# STM32F407_2.net
KiCad netlist of a schematic drawn in Altium Designer
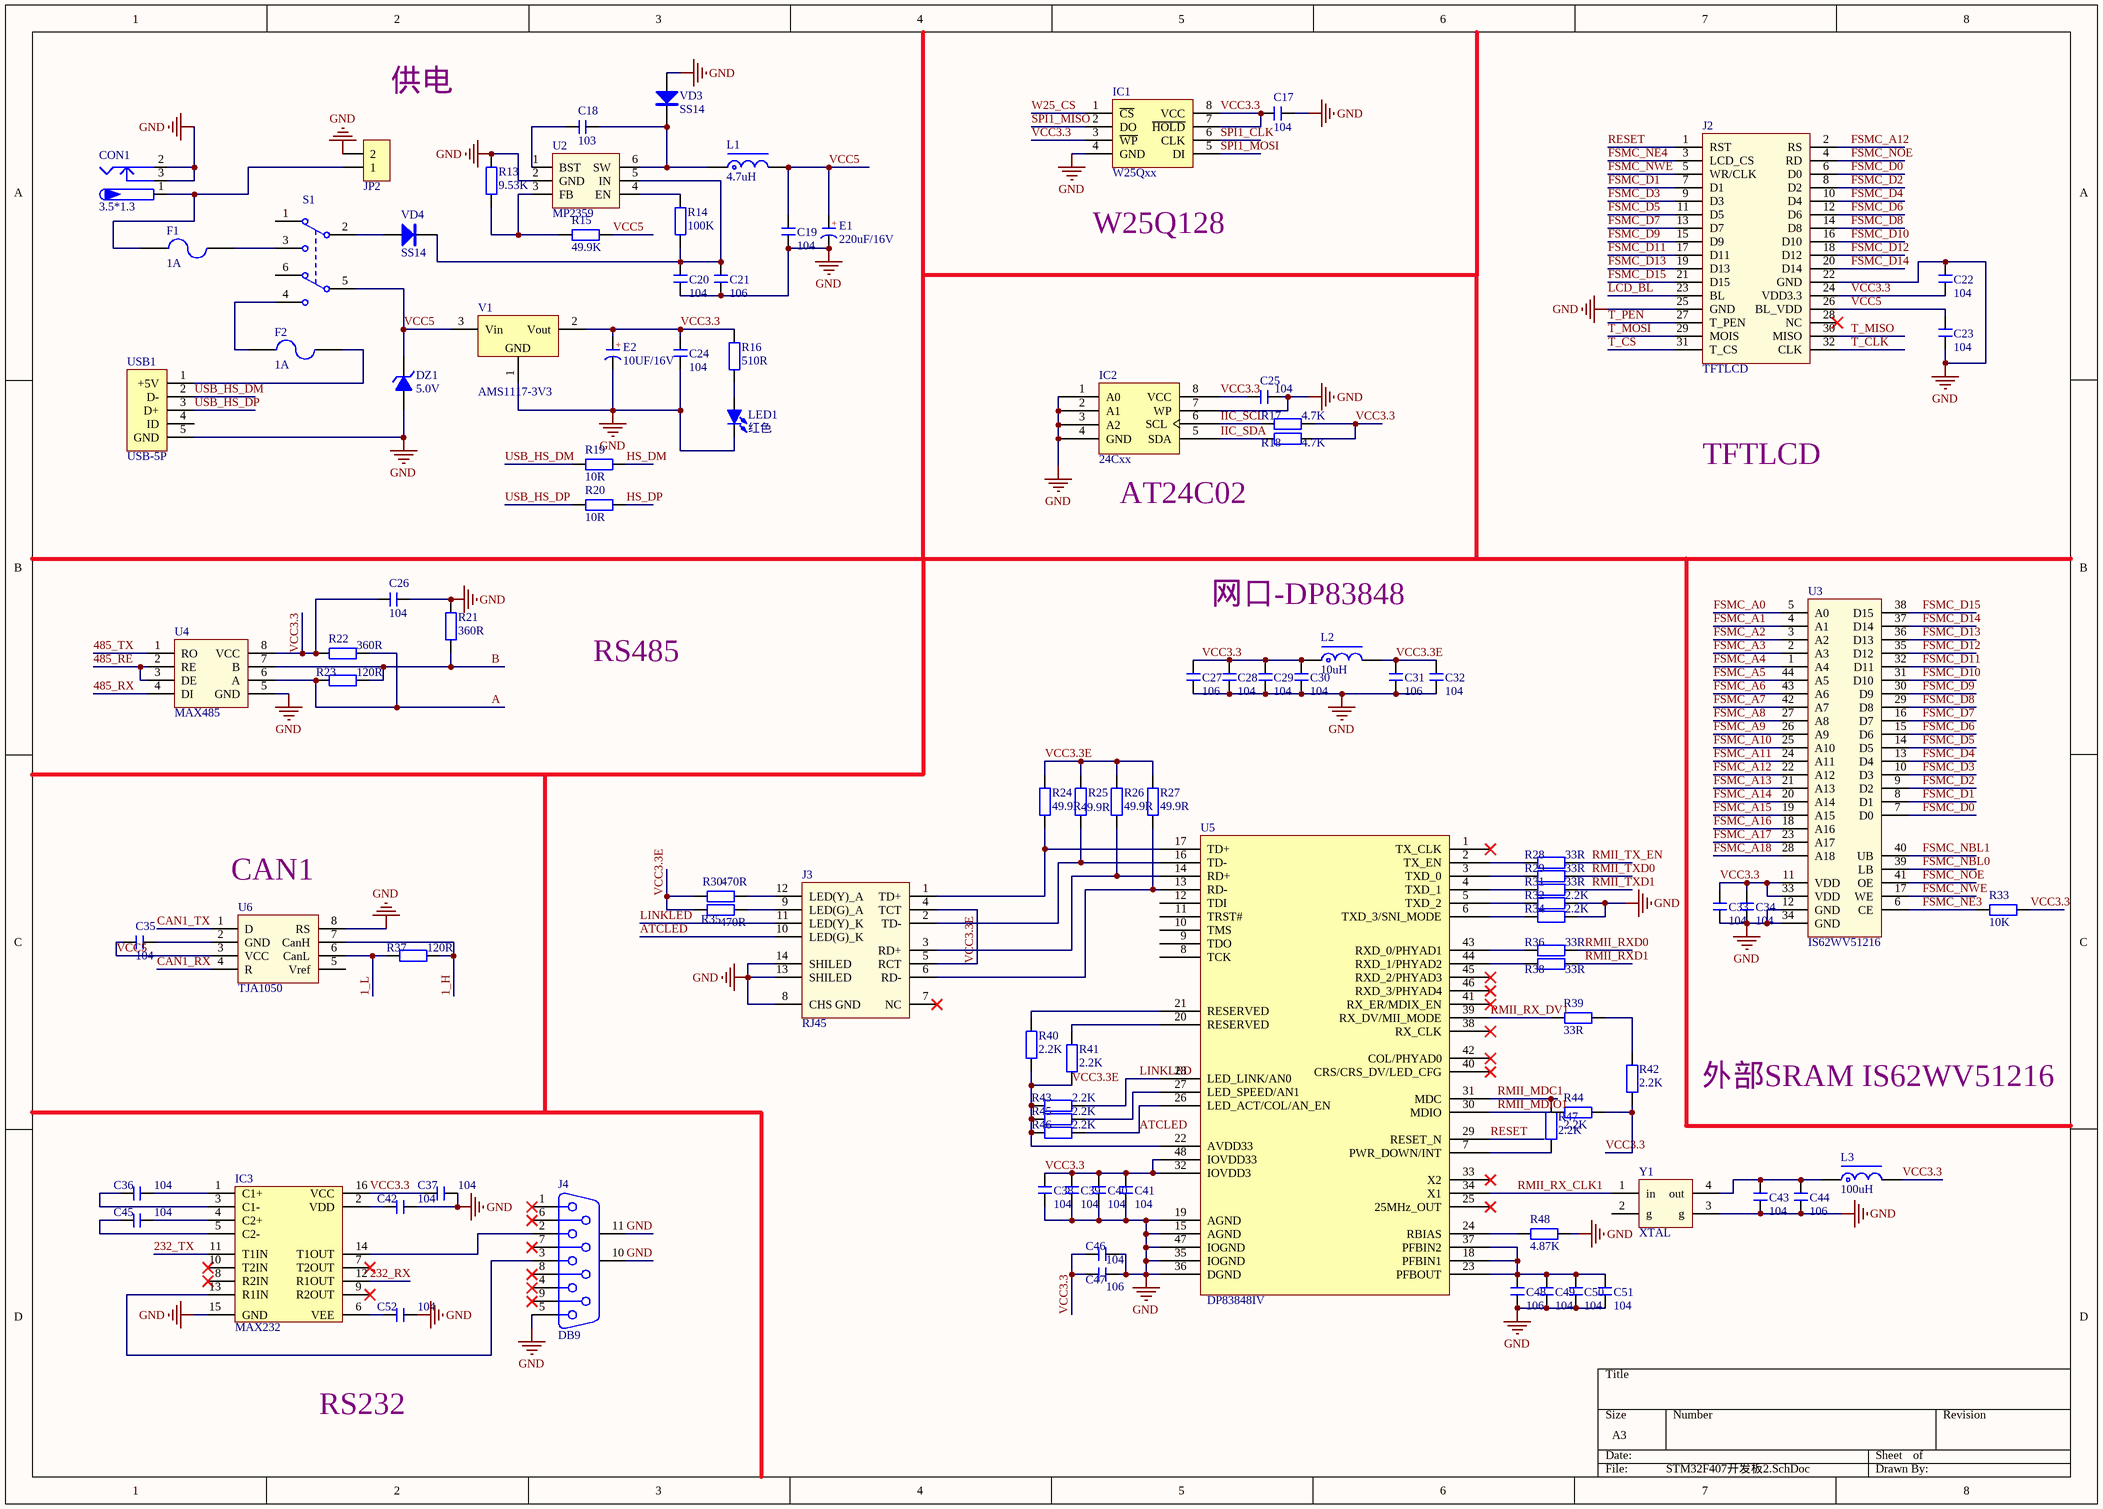
[diagram p0: STM32F407开发板2.SchDoc]

(export (version "E")
  (design (tool "Eeschema 10.0.6"))
  (components
    (comp (ref "C17")
      (value "104")
      (footprint "C 0603")
      (description "无极性贴片电容")
      (libsource (lib "电阻-电容-电感") (part "C"))
    )
    (comp (ref "C18")
      (value "103")
      (footprint "C 0603")
      (description "无极性贴片电容")
      (libsource (lib "电阻-电容-电感") (part "C"))
    )
    (comp (ref "C19")
      (value "104")
      (footprint "C 0603")
      (description "无极性贴片电容")
      (libsource (lib "电阻-电容-电感") (part "C"))
    )
    (comp (ref "C20")
      (value "104")
      (footprint "C 0603")
      (description "无极性贴片电容")
      (libsource (lib "电阻-电容-电感") (part "C"))
    )
    (comp (ref "C21")
      (value "106")
      (footprint "C 0603")
      (description "无极性贴片电容")
      (libsource (lib "电阻-电容-电感") (part "C"))
    )
    (comp (ref "C22")
      (value "104")
      (footprint "C 0603")
      (description "无极性贴片电容")
      (libsource (lib "电阻-电容-电感") (part "C"))
    )
    (comp (ref "C23")
      (value "104")
      (footprint "C 0603")
      (description "无极性贴片电容")
      (libsource (lib "电阻-电容-电感") (part "C"))
    )
    (comp (ref "C24")
      (value "104")
      (footprint "C 0603")
      (description "无极性贴片电容")
      (libsource (lib "电阻-电容-电感") (part "C"))
    )
    (comp (ref "C25")
      (value "104")
      (footprint "C 0603")
      (description "无极性贴片电容")
      (libsource (lib "电阻-电容-电感") (part "C"))
    )
    (comp (ref "C26")
      (value "104")
      (footprint "C 0603")
      (description "无极性贴片电容")
      (libsource (lib "电阻-电容-电感") (part "C"))
    )
    (comp (ref "C27")
      (value "106")
      (footprint "C 0603")
      (description "无极性贴片电容")
      (libsource (lib "电阻-电容-电感") (part "C"))
    )
    (comp (ref "C28")
      (value "104")
      (footprint "C 0603")
      (description "无极性贴片电容")
      (libsource (lib "电阻-电容-电感") (part "C"))
    )
    (comp (ref "C29")
      (value "104")
      (footprint "C 0603")
      (description "无极性贴片电容")
      (libsource (lib "电阻-电容-电感") (part "C"))
    )
    (comp (ref "C30")
      (value "104")
      (footprint "C 0603")
      (description "无极性贴片电容")
      (libsource (lib "电阻-电容-电感") (part "C"))
    )
    (comp (ref "C31")
      (value "106")
      (footprint "C 0603")
      (description "无极性贴片电容")
      (libsource (lib "电阻-电容-电感") (part "C"))
    )
    (comp (ref "C32")
      (value "104")
      (footprint "C 0603")
      (description "无极性贴片电容")
      (libsource (lib "电阻-电容-电感") (part "C"))
    )
    (comp (ref "C33")
      (value "104")
      (footprint "C 0603")
      (description "无极性贴片电容")
      (libsource (lib "电阻-电容-电感") (part "C"))
    )
    (comp (ref "C34")
      (value "104")
      (footprint "C 0603")
      (description "无极性贴片电容")
      (libsource (lib "电阻-电容-电感") (part "C"))
    )
    (comp (ref "C35")
      (value "104")
      (footprint "C 0603")
      (description "无极性贴片电容")
      (libsource (lib "电阻-电容-电感") (part "C"))
    )
    (comp (ref "C36")
      (value "104")
      (footprint "C 0603")
      (description "无极性贴片电容")
      (libsource (lib "电阻-电容-电感") (part "C"))
    )
    (comp (ref "C37")
      (value "104")
      (footprint "C 0603")
      (description "无极性贴片电容")
      (libsource (lib "电阻-电容-电感") (part "C"))
    )
    (comp (ref "C38")
      (value "104")
      (footprint "C 0603")
      (description "无极性贴片电容")
      (libsource (lib "电阻-电容-电感") (part "C"))
    )
    (comp (ref "C39")
      (value "104")
      (footprint "C 0603")
      (description "无极性贴片电容")
      (libsource (lib "电阻-电容-电感") (part "C"))
    )
    (comp (ref "C40")
      (value "104")
      (footprint "C 0603")
      (description "无极性贴片电容")
      (libsource (lib "电阻-电容-电感") (part "C"))
    )
    (comp (ref "C41")
      (value "104")
      (footprint "C 0603")
      (description "无极性贴片电容")
      (libsource (lib "电阻-电容-电感") (part "C"))
    )
    (comp (ref "C42")
      (value "104")
      (footprint "C 0603")
      (description "无极性贴片电容")
      (libsource (lib "电阻-电容-电感") (part "C"))
    )
    (comp (ref "C43")
      (value "104")
      (footprint "C 0603")
      (description "无极性贴片电容")
      (libsource (lib "电阻-电容-电感") (part "C"))
    )
    (comp (ref "C44")
      (value "106")
      (footprint "C 0603")
      (description "无极性贴片电容")
      (libsource (lib "电阻-电容-电感") (part "C"))
    )
    (comp (ref "C45")
      (value "104")
      (footprint "C 0603")
      (description "无极性贴片电容")
      (libsource (lib "电阻-电容-电感") (part "C"))
    )
    (comp (ref "C46")
      (value "104")
      (footprint "C 0603")
      (description "无极性贴片电容")
      (libsource (lib "电阻-电容-电感") (part "C"))
    )
    (comp (ref "C47")
      (value "106")
      (footprint "C 0603")
      (description "无极性贴片电容")
      (libsource (lib "电阻-电容-电感") (part "C"))
    )
    (comp (ref "C48")
      (value "106")
      (footprint "C 0603")
      (description "无极性贴片电容")
      (libsource (lib "电阻-电容-电感") (part "C"))
    )
    (comp (ref "C49")
      (value "104")
      (footprint "C 0603")
      (description "无极性贴片电容")
      (libsource (lib "电阻-电容-电感") (part "C"))
    )
    (comp (ref "C50")
      (value "104")
      (footprint "C 0603")
      (description "无极性贴片电容")
      (libsource (lib "电阻-电容-电感") (part "C"))
    )
    (comp (ref "C51")
      (value "104")
      (footprint "C 0603")
      (description "无极性贴片电容")
      (libsource (lib "电阻-电容-电感") (part "C"))
    )
    (comp (ref "C52")
      (value "104")
      (footprint "C 0603")
      (description "无极性贴片电容")
      (libsource (lib "电阻-电容-电感") (part "C"))
    )
    (comp (ref "CON1")
      (value "3.5*1.3")
      (footprint "DC_5.5MM")
      (description "低压电源接口")
      (libsource (lib "接口类") (part "P-DC"))
    )
    (comp (ref "DZ1")
      (value "5.0V")
      (footprint "MINI_MELF (LL34)")
      (description "12V/0.5W稳压管")
      (libsource (lib "二极管-整流桥") (part "1N4106"))
    )
    (comp (ref "E1")
      (value "220uF/16V")
      (footprint "CM D(6.3*7.7)")
      (description "直插电解电容")
      (libsource (lib "电阻-电容-电感") (part "C-CAP"))
    )
    (comp (ref "E2")
      (value "10UF/16V")
      (footprint "C 1206")
      (description "直插电解电容")
      (libsource (lib "电阻-电容-电感") (part "C-CAP"))
    )
    (comp (ref "F1")
      (value "1A")
      (footprint "L 1206")
      (description "5*20保险丝")
      (libsource (lib "保险丝-晶振") (part "FU 5x20"))
    )
    (comp (ref "F2")
      (value "1A")
      (footprint "L 1206")
      (description "5*20保险丝")
      (libsource (lib "保险丝-晶振") (part "FU 5x20"))
    )
    (comp (ref "IC1")
      (value "W25Qxx")
      (footprint "SOP8W_L")
      (description "外置Flash")
      (libsource (lib "IC芯片") (part "W25Qxx"))
    )
    (comp (ref "IC2")
      (value "24Cxx")
      (footprint "SOP8_L")
      (description "外置EEPROM")
      (libsource (lib "IC芯片") (part "24Cxx"))
    )
    (comp (ref "IC3") (value "MAX232") (footprint "SOP16_L") (libsource (lib "IC芯片") (part "MAX232")))
    (comp (ref "J2") (value "TFTLCD") (footprint "HDR-16X2") (libsource (lib "显示器件") (part "TFTLCD")))
    (comp (ref "J3") (value "RJ45") (footprint "HR911105A") (libsource (lib "IC芯片") (part "RJ45")))
    (comp (ref "J4")
      (value "DB9")
      (footprint "DB9/P_A")
      (description "9针串口")
      (libsource (lib "接口类") (part "DB9"))
    )
    (comp (ref "JP2")
      (value "HDR-1X2")
      (footprint "KF301-2P")
      (description "2P接插件")
      (libsource (lib "接插件") (part "Header 2"))
    )
    (comp (ref "L1")
      (value "4.7uH")
      (footprint "L 0603")
      (description "小功率贴片电感")
      (libsource (lib "电阻-电容-电感") (part "L"))
    )
    (comp (ref "L2")
      (value "10uH")
      (footprint "L 0603")
      (description "小功率贴片电感")
      (libsource (lib "电阻-电容-电感") (part "L"))
    )
    (comp (ref "L3")
      (value "100uH")
      (footprint "L 0603")
      (description "小功率贴片电感")
      (libsource (lib "电阻-电容-电感") (part "L"))
    )
    (comp (ref "LED1")
      (value "红色")
      (footprint "LED 0603R")
      (description "5mm插件LED")
      (libsource (lib "LED") (part "LED-5MM"))
    )
    (comp (ref "R13")
      (value "9.53K")
      (footprint "R 0603")
      (description "贴片电阻")
      (libsource (lib "电阻-电容-电感") (part "R"))
    )
    (comp (ref "R14")
      (value "100K")
      (footprint "R 0603")
      (description "贴片电阻")
      (libsource (lib "电阻-电容-电感") (part "R"))
    )
    (comp (ref "R15")
      (value "49.9K")
      (footprint "R 0603")
      (description "贴片电阻")
      (libsource (lib "电阻-电容-电感") (part "R"))
    )
    (comp (ref "R16")
      (value "510R")
      (footprint "R 0603")
      (description "贴片电阻")
      (libsource (lib "电阻-电容-电感") (part "R"))
    )
    (comp (ref "R17")
      (value "4.7K")
      (footprint "R 0603")
      (description "贴片电阻")
      (libsource (lib "电阻-电容-电感") (part "R"))
    )
    (comp (ref "R18")
      (value "4.7K")
      (footprint "R 0603")
      (description "贴片电阻")
      (libsource (lib "电阻-电容-电感") (part "R"))
    )
    (comp (ref "R19")
      (value "10R")
      (footprint "R 0603")
      (description "贴片电阻")
      (libsource (lib "电阻-电容-电感") (part "R"))
    )
    (comp (ref "R20")
      (value "10R")
      (footprint "R 0603")
      (description "贴片电阻")
      (libsource (lib "电阻-电容-电感") (part "R"))
    )
    (comp (ref "R21")
      (value "360R")
      (footprint "R 0603")
      (description "贴片电阻")
      (libsource (lib "电阻-电容-电感") (part "R"))
    )
    (comp (ref "R22")
      (value "360R")
      (footprint "R 0603")
      (description "贴片电阻")
      (libsource (lib "电阻-电容-电感") (part "R"))
    )
    (comp (ref "R23")
      (value "120R")
      (footprint "R 0603")
      (description "贴片电阻")
      (libsource (lib "电阻-电容-电感") (part "R"))
    )
    (comp (ref "R24")
      (value "49.9R")
      (footprint "R 0603")
      (description "贴片电阻")
      (libsource (lib "电阻-电容-电感") (part "R"))
    )
    (comp (ref "R25")
      (value "49.9R")
      (footprint "R 0603")
      (description "贴片电阻")
      (libsource (lib "电阻-电容-电感") (part "R"))
    )
    (comp (ref "R26")
      (value "49.9R")
      (footprint "R 0603")
      (description "贴片电阻")
      (libsource (lib "电阻-电容-电感") (part "R"))
    )
    (comp (ref "R27")
      (value "49.9R")
      (footprint "R 0603")
      (description "贴片电阻")
      (libsource (lib "电阻-电容-电感") (part "R"))
    )
    (comp (ref "R28")
      (value "33R")
      (footprint "R 0603")
      (description "贴片电阻")
      (libsource (lib "电阻-电容-电感") (part "R"))
    )
    (comp (ref "R29")
      (value "33R")
      (footprint "R 0603")
      (description "贴片电阻")
      (libsource (lib "电阻-电容-电感") (part "R"))
    )
    (comp (ref "R30")
      (value "470R")
      (footprint "R 0603")
      (description "贴片电阻")
      (libsource (lib "电阻-电容-电感") (part "R"))
    )
    (comp (ref "R31")
      (value "33R")
      (footprint "R 0603")
      (description "贴片电阻")
      (libsource (lib "电阻-电容-电感") (part "R"))
    )
    (comp (ref "R32")
      (value "2.2K")
      (footprint "R 0603")
      (description "贴片电阻")
      (libsource (lib "电阻-电容-电感") (part "R"))
    )
    (comp (ref "R33")
      (value "10K")
      (footprint "R 0603")
      (description "贴片电阻")
      (libsource (lib "电阻-电容-电感") (part "R"))
    )
    (comp (ref "R34")
      (value "2.2K")
      (footprint "R 0603")
      (description "贴片电阻")
      (libsource (lib "电阻-电容-电感") (part "R"))
    )
    (comp (ref "R35")
      (value "470R")
      (footprint "R 0603")
      (description "贴片电阻")
      (libsource (lib "电阻-电容-电感") (part "R"))
    )
    (comp (ref "R36")
      (value "33R")
      (footprint "R 0603")
      (description "贴片电阻")
      (libsource (lib "电阻-电容-电感") (part "R"))
    )
    (comp (ref "R37")
      (value "120R")
      (footprint "R 0603")
      (description "贴片电阻")
      (libsource (lib "电阻-电容-电感") (part "R"))
    )
    (comp (ref "R38")
      (value "33R")
      (footprint "R 0603")
      (description "贴片电阻")
      (libsource (lib "电阻-电容-电感") (part "R"))
    )
    (comp (ref "R39")
      (value "33R")
      (footprint "R 0603")
      (description "贴片电阻")
      (libsource (lib "电阻-电容-电感") (part "R"))
    )
    (comp (ref "R40")
      (value "2.2K")
      (footprint "R 0603")
      (description "贴片电阻")
      (libsource (lib "电阻-电容-电感") (part "R"))
    )
    (comp (ref "R41")
      (value "2.2K")
      (footprint "R 0603")
      (description "贴片电阻")
      (libsource (lib "电阻-电容-电感") (part "R"))
    )
    (comp (ref "R42")
      (value "2.2K")
      (footprint "R 0603")
      (description "贴片电阻")
      (libsource (lib "电阻-电容-电感") (part "R"))
    )
    (comp (ref "R43")
      (value "2.2K")
      (footprint "R 0603")
      (description "贴片电阻")
      (libsource (lib "电阻-电容-电感") (part "R"))
    )
    (comp (ref "R44")
      (value "2.2K")
      (footprint "R 0603")
      (description "贴片电阻")
      (libsource (lib "电阻-电容-电感") (part "R"))
    )
    (comp (ref "R45")
      (value "2.2K")
      (footprint "R 0603")
      (description "贴片电阻")
      (libsource (lib "电阻-电容-电感") (part "R"))
    )
    (comp (ref "R46")
      (value "2.2K")
      (footprint "R 0603")
      (description "贴片电阻")
      (libsource (lib "电阻-电容-电感") (part "R"))
    )
    (comp (ref "R47")
      (value "2.2K")
      (footprint "R 0603")
      (description "贴片电阻")
      (libsource (lib "电阻-电容-电感") (part "R"))
    )
    (comp (ref "R48")
      (value "4.87K")
      (footprint "R 0603")
      (description "贴片电阻")
      (libsource (lib "电阻-电容-电感") (part "R"))
    )
    (comp (ref "S1")
      (value "SK-22D02")
      (footprint "KFT DIP-8X8")
      (description "2路波动开关")
      (libsource (lib "按键-开关") (part "SSW-2P"))
    )
    (comp (ref "U2") (value "MP2359") (footprint "MP2359") (libsource (lib "IC芯片") (part "MP2359")))
    (comp (ref "U3")
      (value "IS62WV51216")
      (footprint "IS62WV51216")
      (libsource (lib "IC芯片") (part "IS62WV51216"))
    )
    (comp (ref "U4") (value "MAX485") (footprint "MAX485") (libsource (lib "IC芯片") (part "MAX485")))
    (comp (ref "U5")
      (value "DP83848IV")
      (footprint "LQFP48 7X7_L")
      (libsource (lib "IC芯片") (part "DP83848IV"))
    )
    (comp (ref "U6") (value "TJA1050") (footprint "TJA1050") (libsource (lib "IC芯片") (part "TJA1050")))
    (comp (ref "USB1")
      (value "USB-5P")
      (footprint "USB-MINI-A")
      (description "微型USB母座")
      (libsource (lib "接口类") (part "USB-5P"))
    )
    (comp (ref "V1")
      (value "AMS1117-3V3")
      (footprint "SOT223_L")
      (description "三端稳压芯片")
      (libsource (lib "IC芯片") (part "AMS1117"))
    )
    (comp (ref "VD3")
      (value "SS14")
      (footprint "SOD-123")
      (description "肖特基二极管")
      (libsource (lib "二极管-整流桥") (part "SS14"))
    )
    (comp (ref "VD4")
      (value "SS14")
      (footprint "SOD-123")
      (description "肖特基二极管")
      (libsource (lib "二极管-整流桥") (part "SS14"))
    )
    (comp (ref "Y1") (value "XTAL") (footprint "XTAL-5032") (libsource (lib "保险丝-晶振") (part "XTAL")))
  )
  (nets
    (net (code "1") (name "/1_H") (class "Default")
      (node (ref "R37") (pin "1") (pinfunction "1_1") (pintype "passive"))
      (node (ref "U6") (pin "7") (pinfunction "CanH_7") (pintype "passive"))
    )
    (net (code "2") (name "/1_L") (class "Default")
      (node (ref "R37") (pin "2") (pinfunction "2_2") (pintype "passive"))
      (node (ref "U6") (pin "6") (pinfunction "CanL_6") (pintype "passive"))
    )
    (net (code "3") (name "/232_RX") (class "Default")
      (node (ref "IC3") (pin "12") (pinfunction "R1OUT_12") (pintype "passive"))
    )
    (net (code "4") (name "/232_TX") (class "Default")
      (node (ref "IC3") (pin "11") (pinfunction "T1IN_11") (pintype "passive"))
    )
    (net (code "5") (name "/485_RE") (class "Default")
      (node (ref "U4") (pin "2") (pinfunction "RE_2") (pintype "passive"))
      (node (ref "U4") (pin "3") (pinfunction "DE_3") (pintype "passive"))
    )
    (net (code "6") (name "/485_RX") (class "Default")
      (node (ref "U4") (pin "4") (pinfunction "DI_4") (pintype "passive"))
    )
    (net (code "7") (name "/485_TX") (class "Default")
      (node (ref "U4") (pin "1") (pinfunction "RO_1") (pintype "passive"))
    )
    (net (code "8") (name "/A") (class "Default")
      (node (ref "R22") (pin "1") (pinfunction "1_1") (pintype "passive"))
      (node (ref "R23") (pin "2") (pinfunction "2_2") (pintype "passive"))
      (node (ref "U4") (pin "6") (pinfunction "A_6") (pintype "passive"))
    )
    (net (code "9") (name "/ATCLED") (class "Default")
      (node (ref "J3") (pin "10") (pinfunction "LED(G)_K_10") (pintype "passive"))
      (node (ref "R46") (pin "1") (pinfunction "1_1") (pintype "passive"))
      (node (ref "U5") (pin "26") (pinfunction "LED_ACT/COL/AN_EN_26") (pintype "passive"))
    )
    (net (code "10") (name "/B") (class "Default")
      (node (ref "R21") (pin "2") (pinfunction "2_2") (pintype "passive"))
      (node (ref "R23") (pin "1") (pinfunction "1_1") (pintype "passive"))
      (node (ref "U4") (pin "7") (pinfunction "B_7") (pintype "passive"))
    )
    (net (code "11") (name "/CAN1_RX") (class "Default")
      (node (ref "U6") (pin "4") (pinfunction "R_4") (pintype "passive"))
    )
    (net (code "12") (name "/CAN1_TX") (class "Default")
      (node (ref "U6") (pin "1") (pinfunction "D_1") (pintype "passive"))
    )
    (net (code "13") (name "/FSMC_A0") (class "Default")
      (node (ref "U3") (pin "5") (pinfunction "A0_5") (pintype "passive"))
    )
    (net (code "14") (name "/FSMC_A1") (class "Default")
      (node (ref "U3") (pin "4") (pinfunction "A1_4") (pintype "passive"))
    )
    (net (code "15") (name "/FSMC_A2") (class "Default")
      (node (ref "U3") (pin "3") (pinfunction "A2_3") (pintype "passive"))
    )
    (net (code "16") (name "/FSMC_A3") (class "Default")
      (node (ref "U3") (pin "2") (pinfunction "A3_2") (pintype "passive"))
    )
    (net (code "17") (name "/FSMC_A4") (class "Default")
      (node (ref "U3") (pin "1") (pinfunction "A4_1") (pintype "passive"))
    )
    (net (code "18") (name "/FSMC_A5") (class "Default")
      (node (ref "U3") (pin "44") (pinfunction "A5_44") (pintype "passive"))
    )
    (net (code "19") (name "/FSMC_A6") (class "Default")
      (node (ref "U3") (pin "43") (pinfunction "A6_43") (pintype "passive"))
    )
    (net (code "20") (name "/FSMC_A7") (class "Default")
      (node (ref "U3") (pin "42") (pinfunction "A7_42") (pintype "passive"))
    )
    (net (code "21") (name "/FSMC_A8") (class "Default")
      (node (ref "U3") (pin "27") (pinfunction "A8_27") (pintype "passive"))
    )
    (net (code "22") (name "/FSMC_A9") (class "Default")
      (node (ref "U3") (pin "26") (pinfunction "A9_26") (pintype "passive"))
    )
    (net (code "23") (name "/FSMC_A10") (class "Default")
      (node (ref "U3") (pin "25") (pinfunction "A10_25") (pintype "passive"))
    )
    (net (code "24") (name "/FSMC_A11") (class "Default")
      (node (ref "U3") (pin "24") (pinfunction "A11_24") (pintype "passive"))
    )
    (net (code "25") (name "/FSMC_A12") (class "Default")
      (node (ref "J2") (pin "2") (pinfunction "RS_2") (pintype "passive"))
      (node (ref "U3") (pin "22") (pinfunction "A12_22") (pintype "passive"))
    )
    (net (code "26") (name "/FSMC_A13") (class "Default")
      (node (ref "U3") (pin "21") (pinfunction "A13_21") (pintype "passive"))
    )
    (net (code "27") (name "/FSMC_A14") (class "Default")
      (node (ref "U3") (pin "20") (pinfunction "A14_20") (pintype "passive"))
    )
    (net (code "28") (name "/FSMC_A15") (class "Default")
      (node (ref "U3") (pin "19") (pinfunction "A15_19") (pintype "passive"))
    )
    (net (code "29") (name "/FSMC_A16") (class "Default")
      (node (ref "U3") (pin "18") (pinfunction "A16_18") (pintype "passive"))
    )
    (net (code "30") (name "/FSMC_A17") (class "Default")
      (node (ref "U3") (pin "23") (pinfunction "A17_23") (pintype "passive"))
    )
    (net (code "31") (name "/FSMC_A18") (class "Default")
      (node (ref "U3") (pin "28") (pinfunction "A18_28") (pintype "passive"))
    )
    (net (code "32") (name "/FSMC_D0") (class "Default")
      (node (ref "J2") (pin "6") (pinfunction "D0_6") (pintype "passive"))
      (node (ref "U3") (pin "7") (pinfunction "D0_7") (pintype "passive"))
    )
    (net (code "33") (name "/FSMC_D1") (class "Default")
      (node (ref "J2") (pin "7") (pinfunction "D1_7") (pintype "passive"))
      (node (ref "U3") (pin "8") (pinfunction "D1_8") (pintype "passive"))
    )
    (net (code "34") (name "/FSMC_D2") (class "Default")
      (node (ref "J2") (pin "8") (pinfunction "D2_8") (pintype "passive"))
      (node (ref "U3") (pin "9") (pinfunction "D2_9") (pintype "passive"))
    )
    (net (code "35") (name "/FSMC_D3") (class "Default")
      (node (ref "J2") (pin "9") (pinfunction "D3_9") (pintype "passive"))
      (node (ref "U3") (pin "10") (pinfunction "D3_10") (pintype "passive"))
    )
    (net (code "36") (name "/FSMC_D4") (class "Default")
      (node (ref "J2") (pin "10") (pinfunction "D4_10") (pintype "passive"))
      (node (ref "U3") (pin "13") (pinfunction "D4_13") (pintype "passive"))
    )
    (net (code "37") (name "/FSMC_D5") (class "Default")
      (node (ref "J2") (pin "11") (pinfunction "D5_11") (pintype "passive"))
      (node (ref "U3") (pin "14") (pinfunction "D5_14") (pintype "passive"))
    )
    (net (code "38") (name "/FSMC_D6") (class "Default")
      (node (ref "J2") (pin "12") (pinfunction "D6_12") (pintype "passive"))
      (node (ref "U3") (pin "15") (pinfunction "D6_15") (pintype "passive"))
    )
    (net (code "39") (name "/FSMC_D7") (class "Default")
      (node (ref "J2") (pin "13") (pinfunction "D7_13") (pintype "passive"))
      (node (ref "U3") (pin "16") (pinfunction "D7_16") (pintype "passive"))
    )
    (net (code "40") (name "/FSMC_D8") (class "Default")
      (node (ref "J2") (pin "14") (pinfunction "D8_14") (pintype "passive"))
      (node (ref "U3") (pin "29") (pinfunction "D8_29") (pintype "passive"))
    )
    (net (code "41") (name "/FSMC_D9") (class "Default")
      (node (ref "J2") (pin "15") (pinfunction "D9_15") (pintype "passive"))
      (node (ref "U3") (pin "30") (pinfunction "D9_30") (pintype "passive"))
    )
    (net (code "42") (name "/FSMC_D10") (class "Default")
      (node (ref "J2") (pin "16") (pinfunction "D10_16") (pintype "passive"))
      (node (ref "U3") (pin "31") (pinfunction "D10_31") (pintype "passive"))
    )
    (net (code "43") (name "/FSMC_D11") (class "Default")
      (node (ref "J2") (pin "17") (pinfunction "D11_17") (pintype "passive"))
      (node (ref "U3") (pin "32") (pinfunction "D11_32") (pintype "passive"))
    )
    (net (code "44") (name "/FSMC_D12") (class "Default")
      (node (ref "J2") (pin "18") (pinfunction "D12_18") (pintype "passive"))
      (node (ref "U3") (pin "35") (pinfunction "D12_35") (pintype "passive"))
    )
    (net (code "45") (name "/FSMC_D13") (class "Default")
      (node (ref "J2") (pin "19") (pinfunction "D13_19") (pintype "passive"))
      (node (ref "U3") (pin "36") (pinfunction "D13_36") (pintype "passive"))
    )
    (net (code "46") (name "/FSMC_D14") (class "Default")
      (node (ref "J2") (pin "20") (pinfunction "D14_20") (pintype "passive"))
      (node (ref "U3") (pin "37") (pinfunction "D14_37") (pintype "passive"))
    )
    (net (code "47") (name "/FSMC_D15") (class "Default")
      (node (ref "J2") (pin "21") (pinfunction "D15_21") (pintype "passive"))
      (node (ref "U3") (pin "38") (pinfunction "D15_38") (pintype "passive"))
    )
    (net (code "48") (name "/FSMC_NBL0") (class "Default")
      (node (ref "U3") (pin "39") (pinfunction "LB_39") (pintype "passive"))
    )
    (net (code "49") (name "/FSMC_NBL1") (class "Default")
      (node (ref "U3") (pin "40") (pinfunction "UB_40") (pintype "passive"))
    )
    (net (code "50") (name "/FSMC_NE3") (class "Default")
      (node (ref "R33") (pin "2") (pinfunction "2_2") (pintype "passive"))
      (node (ref "U3") (pin "6") (pinfunction "CE_6") (pintype "passive"))
    )
    (net (code "51") (name "/FSMC_NE4") (class "Default")
      (node (ref "J2") (pin "3") (pinfunction "LCD_CS_3") (pintype "passive"))
    )
    (net (code "52") (name "/FSMC_NOE") (class "Default")
      (node (ref "J2") (pin "4") (pinfunction "RD_4") (pintype "passive"))
      (node (ref "U3") (pin "41") (pinfunction "OE_41") (pintype "passive"))
    )
    (net (code "53") (name "/FSMC_NWE") (class "Default")
      (node (ref "J2") (pin "5") (pinfunction "WR/CLK_5") (pintype "passive"))
      (node (ref "U3") (pin "17") (pinfunction "WE_17") (pintype "passive"))
    )
    (net (code "54") (name "/HS_DM") (class "Default")
      (node (ref "R19") (pin "1") (pinfunction "1_1") (pintype "passive"))
    )
    (net (code "55") (name "/HS_DP") (class "Default")
      (node (ref "R20") (pin "1") (pinfunction "1_1") (pintype "passive"))
    )
    (net (code "56") (name "/IIC_SCL") (class "Default")
      (node (ref "IC2") (pin "6") (pinfunction "SCL_6") (pintype "passive"))
      (node (ref "R17") (pin "2") (pinfunction "2_2") (pintype "passive"))
    )
    (net (code "57") (name "/IIC_SDA") (class "Default")
      (node (ref "IC2") (pin "5") (pinfunction "SDA_5") (pintype "passive"))
      (node (ref "R18") (pin "2") (pinfunction "2_2") (pintype "passive"))
    )
    (net (code "58") (name "/LCD_BL") (class "Default")
      (node (ref "J2") (pin "23") (pinfunction "BL_23") (pintype "passive"))
    )
    (net (code "59") (name "/LINKLED") (class "Default")
      (node (ref "J3") (pin "11") (pinfunction "LED(Y)_K_11") (pintype "passive"))
      (node (ref "R43") (pin "1") (pinfunction "1_1") (pintype "passive"))
      (node (ref "U5") (pin "28") (pinfunction "LED_LINK/AN0_28") (pintype "passive"))
    )
    (net (code "60") (name "/RESET") (class "Default")
      (node (ref "J2") (pin "1") (pinfunction "RST_1") (pintype "passive"))
      (node (ref "U5") (pin "29") (pinfunction "RESET_N_29") (pintype "passive"))
    )
    (net (code "61") (name "/RMII_MDC1") (class "Default")
      (node (ref "R47") (pin "2") (pinfunction "2_2") (pintype "passive"))
      (node (ref "U5") (pin "31") (pinfunction "MDC_31") (pintype "passive"))
    )
    (net (code "62") (name "/RMII_MDIO1") (class "Default")
      (node (ref "R44") (pin "1") (pinfunction "1_1") (pintype "passive"))
      (node (ref "U5") (pin "30") (pinfunction "MDIO_30") (pintype "passive"))
    )
    (net (code "63") (name "/RMII_RXD0") (class "Default")
      (node (ref "R36") (pin "2") (pinfunction "2_2") (pintype "passive"))
    )
    (net (code "64") (name "/RMII_RXD1") (class "Default")
      (node (ref "R38") (pin "2") (pinfunction "2_2") (pintype "passive"))
    )
    (net (code "65") (name "/RMII_RX_CLK1") (class "Default")
      (node (ref "U5") (pin "34") (pinfunction "X1_34") (pintype "passive"))
      (node (ref "Y1") (pin "1") (pinfunction "in_1") (pintype "passive"))
    )
    (net (code "66") (name "/RMII_RX_DV1") (class "Default")
      (node (ref "R39") (pin "1") (pinfunction "1_1") (pintype "passive"))
      (node (ref "U5") (pin "39") (pinfunction "RX_DV/MII_MODE_39") (pintype "passive"))
    )
    (net (code "67") (name "/RMII_TXD0") (class "Default")
      (node (ref "R29") (pin "2") (pinfunction "2_2") (pintype "passive"))
    )
    (net (code "68") (name "/RMII_TXD1") (class "Default")
      (node (ref "R31") (pin "2") (pinfunction "2_2") (pintype "passive"))
    )
    (net (code "69") (name "/RMII_TX_EN") (class "Default")
      (node (ref "R28") (pin "2") (pinfunction "2_2") (pintype "passive"))
    )
    (net (code "70") (name "/SPI1_CLK") (class "Default")
      (node (ref "IC1") (pin "6") (pinfunction "CLK_6") (pintype "passive"))
    )
    (net (code "71") (name "/SPI1_MISO") (class "Default")
      (node (ref "IC1") (pin "2") (pinfunction "DO_2") (pintype "passive"))
    )
    (net (code "72") (name "/SPI1_MOSI") (class "Default")
      (node (ref "IC1") (pin "5") (pinfunction "DI_5") (pintype "passive"))
    )
    (net (code "73") (name "/T_CLK") (class "Default")
      (node (ref "J2") (pin "32") (pinfunction "CLK_32") (pintype "passive"))
    )
    (net (code "74") (name "/T_CS") (class "Default")
      (node (ref "J2") (pin "31") (pinfunction "T_CS_31") (pintype "passive"))
    )
    (net (code "75") (name "/T_MISO") (class "Default")
      (node (ref "J2") (pin "30") (pinfunction "MISO_30") (pintype "passive"))
    )
    (net (code "76") (name "/T_MOSI") (class "Default")
      (node (ref "J2") (pin "29") (pinfunction "MOIS_29") (pintype "passive"))
    )
    (net (code "77") (name "/T_PEN") (class "Default")
      (node (ref "J2") (pin "27") (pinfunction "T_PEN_27") (pintype "passive"))
    )
    (net (code "78") (name "/USB_HS_DM") (class "Default")
      (node (ref "R19") (pin "2") (pinfunction "2_2") (pintype "passive"))
      (node (ref "USB1") (pin "2") (pinfunction "D-_2") (pintype "passive"))
    )
    (net (code "79") (name "/USB_HS_DP") (class "Default")
      (node (ref "R20") (pin "2") (pinfunction "2_2") (pintype "passive"))
      (node (ref "USB1") (pin "3") (pinfunction "D+_3") (pintype "passive"))
    )
    (net (code "80") (name "/VCC3.3") (class "Default")
      (node (ref "C17") (pin "2") (pinfunction "2_2") (pintype "passive"))
      (node (ref "C22") (pin "2") (pinfunction "2_2") (pintype "passive"))
      (node (ref "C24") (pin "2") (pinfunction "2_2") (pintype "passive"))
      (node (ref "C25") (pin "2") (pinfunction "2_2") (pintype "passive"))
      (node (ref "C26") (pin "2") (pinfunction "2_2") (pintype "passive"))
      (node (ref "C27") (pin "1") (pinfunction "1_1") (pintype "passive"))
      (node (ref "C28") (pin "1") (pinfunction "1_1") (pintype "passive"))
      (node (ref "C29") (pin "1") (pinfunction "1_1") (pintype "passive"))
      (node (ref "C30") (pin "1") (pinfunction "1_1") (pintype "passive"))
      (node (ref "C33") (pin "1") (pinfunction "1_1") (pintype "passive"))
      (node (ref "C34") (pin "1") (pinfunction "1_1") (pintype "passive"))
      (node (ref "C37") (pin "2") (pinfunction "2_2") (pintype "passive"))
      (node (ref "C38") (pin "1") (pinfunction "1_1") (pintype "passive"))
      (node (ref "C39") (pin "1") (pinfunction "1_1") (pintype "passive"))
      (node (ref "C40") (pin "1") (pinfunction "1_1") (pintype "passive"))
      (node (ref "C41") (pin "1") (pinfunction "1_1") (pintype "passive"))
      (node (ref "C46") (pin "1") (pinfunction "1_1") (pintype "passive"))
      (node (ref "C47") (pin "1") (pinfunction "1_1") (pintype "passive"))
      (node (ref "E2") (pin "1") (pinfunction "A_1") (pintype "passive"))
      (node (ref "IC1") (pin "3") (pinfunction "~{WP}_3") (pintype "passive"))
      (node (ref "IC1") (pin "7") (pinfunction "~{HOLD}_7") (pintype "passive"))
      (node (ref "IC1") (pin "8") (pinfunction "VCC_8") (pintype "passive"))
      (node (ref "IC2") (pin "8") (pinfunction "VCC_8") (pintype "power_in"))
      (node (ref "IC3") (pin "16") (pinfunction "VCC_16") (pintype "passive"))
      (node (ref "J2") (pin "24") (pinfunction "VDD3.3_24") (pintype "passive"))
      (node (ref "L2") (pin "1") (pinfunction "1_1") (pintype "passive"))
      (node (ref "L3") (pin "2") (pinfunction "2_2") (pintype "passive"))
      (node (ref "R16") (pin "2") (pinfunction "2_2") (pintype "passive"))
      (node (ref "R17") (pin "1") (pinfunction "1_1") (pintype "passive"))
      (node (ref "R18") (pin "1") (pinfunction "1_1") (pintype "passive"))
      (node (ref "R22") (pin "2") (pinfunction "2_2") (pintype "passive"))
      (node (ref "R33") (pin "1") (pinfunction "1_1") (pintype "passive"))
      (node (ref "R42") (pin "1") (pinfunction "1_1") (pintype "passive"))
      (node (ref "R44") (pin "2") (pinfunction "2_2") (pintype "passive"))
      (node (ref "U3") (pin "11") (pinfunction "VDD_11") (pintype "passive"))
      (node (ref "U3") (pin "33") (pinfunction "VDD_33") (pintype "passive"))
      (node (ref "U4") (pin "8") (pinfunction "VCC_8") (pintype "passive"))
      (node (ref "U5") (pin "32") (pinfunction "IOVDD3_32") (pintype "passive"))
      (node (ref "U5") (pin "48") (pinfunction "IOVDD33_48") (pintype "passive"))
      (node (ref "V1") (pin "2") (pinfunction "Vout_2") (pintype "passive"))
    )
    (net (code "81") (name "/VCC3.3E") (class "Default")
      (node (ref "C31") (pin "1") (pinfunction "1_1") (pintype "passive"))
      (node (ref "C32") (pin "1") (pinfunction "1_1") (pintype "passive"))
      (node (ref "J3") (pin "4") (pinfunction "TCT_4") (pintype "passive"))
      (node (ref "J3") (pin "5") (pinfunction "RCT_5") (pintype "passive"))
      (node (ref "L2") (pin "2") (pinfunction "2_2") (pintype "passive"))
      (node (ref "R24") (pin "1") (pinfunction "1_1") (pintype "passive"))
      (node (ref "R25") (pin "1") (pinfunction "1_1") (pintype "passive"))
      (node (ref "R26") (pin "1") (pinfunction "1_1") (pintype "passive"))
      (node (ref "R27") (pin "1") (pinfunction "1_1") (pintype "passive"))
      (node (ref "R30") (pin "2") (pinfunction "2_2") (pintype "passive"))
      (node (ref "R35") (pin "2") (pinfunction "2_2") (pintype "passive"))
      (node (ref "R40") (pin "2") (pinfunction "2_2") (pintype "passive"))
      (node (ref "R41") (pin "2") (pinfunction "2_2") (pintype "passive"))
      (node (ref "R43") (pin "2") (pinfunction "2_2") (pintype "passive"))
      (node (ref "R45") (pin "2") (pinfunction "2_2") (pintype "passive"))
      (node (ref "R46") (pin "2") (pinfunction "2_2") (pintype "passive"))
      (node (ref "U5") (pin "22") (pinfunction "AVDD33_22") (pintype "passive"))
    )
    (net (code "82") (name "/VCC5") (class "Default")
      (node (ref "C19") (pin "2") (pinfunction "2_2") (pintype "passive"))
      (node (ref "C23") (pin "1") (pinfunction "1_1") (pintype "passive"))
      (node (ref "C35") (pin "2") (pinfunction "2_2") (pintype "passive"))
      (node (ref "DZ1") (pin "2") (pinfunction "K_2") (pintype "passive"))
      (node (ref "E1") (pin "1") (pinfunction "A_1") (pintype "passive"))
      (node (ref "J2") (pin "26") (pinfunction "BL_VDD_26") (pintype "passive"))
      (node (ref "L1") (pin "2") (pinfunction "2_2") (pintype "passive"))
      (node (ref "R15") (pin "1") (pinfunction "1_1") (pintype "passive"))
      (node (ref "S1") (pin "5") (pinfunction "5_5") (pintype "passive"))
      (node (ref "U6") (pin "3") (pinfunction "VCC_3") (pintype "passive"))
      (node (ref "V1") (pin "3") (pinfunction "Vin_3") (pintype "passive"))
    )
    (net (code "83") (name "/W25_CS") (class "Default")
      (node (ref "IC1") (pin "1") (pinfunction "~{CS}_1") (pintype "passive"))
    )
    (net (code "84") (name "GND") (class "Default")
      (node (ref "C17") (pin "1") (pinfunction "1_1") (pintype "passive"))
      (node (ref "C19") (pin "1") (pinfunction "1_1") (pintype "passive"))
      (node (ref "C20") (pin "1") (pinfunction "1_1") (pintype "passive"))
      (node (ref "C21") (pin "1") (pinfunction "1_1") (pintype "passive"))
      (node (ref "C22") (pin "1") (pinfunction "1_1") (pintype "passive"))
      (node (ref "C23") (pin "2") (pinfunction "2_2") (pintype "passive"))
      (node (ref "C24") (pin "1") (pinfunction "1_1") (pintype "passive"))
      (node (ref "C25") (pin "1") (pinfunction "1_1") (pintype "passive"))
      (node (ref "C26") (pin "1") (pinfunction "1_1") (pintype "passive"))
      (node (ref "C27") (pin "2") (pinfunction "2_2") (pintype "passive"))
      (node (ref "C28") (pin "2") (pinfunction "2_2") (pintype "passive"))
      (node (ref "C29") (pin "2") (pinfunction "2_2") (pintype "passive"))
      (node (ref "C30") (pin "2") (pinfunction "2_2") (pintype "passive"))
      (node (ref "C31") (pin "2") (pinfunction "2_2") (pintype "passive"))
      (node (ref "C32") (pin "2") (pinfunction "2_2") (pintype "passive"))
      (node (ref "C33") (pin "2") (pinfunction "2_2") (pintype "passive"))
      (node (ref "C34") (pin "2") (pinfunction "2_2") (pintype "passive"))
      (node (ref "C37") (pin "1") (pinfunction "1_1") (pintype "passive"))
      (node (ref "C38") (pin "2") (pinfunction "2_2") (pintype "passive"))
      (node (ref "C39") (pin "2") (pinfunction "2_2") (pintype "passive"))
      (node (ref "C40") (pin "2") (pinfunction "2_2") (pintype "passive"))
      (node (ref "C41") (pin "2") (pinfunction "2_2") (pintype "passive"))
      (node (ref "C42") (pin "1") (pinfunction "1_1") (pintype "passive"))
      (node (ref "C43") (pin "2") (pinfunction "2_2") (pintype "passive"))
      (node (ref "C44") (pin "2") (pinfunction "2_2") (pintype "passive"))
      (node (ref "C46") (pin "2") (pinfunction "2_2") (pintype "passive"))
      (node (ref "C47") (pin "2") (pinfunction "2_2") (pintype "passive"))
      (node (ref "C48") (pin "2") (pinfunction "2_2") (pintype "passive"))
      (node (ref "C49") (pin "2") (pinfunction "2_2") (pintype "passive"))
      (node (ref "C50") (pin "2") (pinfunction "2_2") (pintype "passive"))
      (node (ref "C51") (pin "2") (pinfunction "2_2") (pintype "passive"))
      (node (ref "C52") (pin "1") (pinfunction "1_1") (pintype "passive"))
      (node (ref "CON1") (pin "2") (pintype "power_in"))
      (node (ref "CON1") (pin "3") (pintype "power_in"))
      (node (ref "DZ1") (pin "1") (pinfunction "A_1") (pintype "passive"))
      (node (ref "E1") (pin "2") (pinfunction "K_2") (pintype "passive"))
      (node (ref "E2") (pin "2") (pinfunction "K_2") (pintype "passive"))
      (node (ref "IC1") (pin "4") (pinfunction "GND_4") (pintype "passive"))
      (node (ref "IC2") (pin "1") (pinfunction "A0_1") (pintype "passive"))
      (node (ref "IC2") (pin "2") (pinfunction "A1_2") (pintype "passive"))
      (node (ref "IC2") (pin "3") (pinfunction "A2_3") (pintype "passive"))
      (node (ref "IC2") (pin "4") (pinfunction "GND_4") (pintype "passive"))
      (node (ref "IC2") (pin "7") (pinfunction "WP_7") (pintype "passive"))
      (node (ref "IC3") (pin "15") (pinfunction "GND_15") (pintype "passive"))
      (node (ref "J2") (pin "22") (pinfunction "GND_22") (pintype "passive"))
      (node (ref "J2") (pin "25") (pinfunction "GND_25") (pintype "passive"))
      (node (ref "J3") (pin "13") (pinfunction "SHILED_13") (pintype "passive"))
      (node (ref "J3") (pin "14") (pinfunction "SHILED_14") (pintype "passive"))
      (node (ref "J3") (pin "8") (pinfunction "CHS_GND_8") (pintype "passive"))
      (node (ref "J4") (pin "10") (pinfunction "MH1_10") (pintype "passive"))
      (node (ref "J4") (pin "11") (pinfunction "MH2_11") (pintype "passive"))
      (node (ref "J4") (pin "5") (pinfunction "5_5") (pintype "passive"))
      (node (ref "JP2") (pin "2") (pinfunction "2_2") (pintype "passive"))
      (node (ref "LED1") (pin "2") (pinfunction "K_2") (pintype "passive"))
      (node (ref "R13") (pin "2") (pinfunction "2_2") (pintype "passive"))
      (node (ref "R21") (pin "1") (pinfunction "1_1") (pintype "passive"))
      (node (ref "R32") (pin "2") (pinfunction "2_2") (pintype "passive"))
      (node (ref "R34") (pin "2") (pinfunction "2_2") (pintype "passive"))
      (node (ref "R48") (pin "2") (pinfunction "2_2") (pintype "passive"))
      (node (ref "U2") (pin "2") (pinfunction "GND_2") (pintype "passive"))
      (node (ref "U3") (pin "12") (pinfunction "GND_12") (pintype "passive"))
      (node (ref "U3") (pin "34") (pinfunction "GND_34") (pintype "passive"))
      (node (ref "U4") (pin "5") (pinfunction "GND_5") (pintype "passive"))
      (node (ref "U5") (pin "15") (pinfunction "AGND_15") (pintype "passive"))
      (node (ref "U5") (pin "19") (pinfunction "AGND_19") (pintype "passive"))
      (node (ref "U5") (pin "35") (pinfunction "IOGND_35") (pintype "passive"))
      (node (ref "U5") (pin "36") (pinfunction "DGND_36") (pintype "passive"))
      (node (ref "U5") (pin "47") (pinfunction "IOGND_47") (pintype "passive"))
      (node (ref "U6") (pin "8") (pinfunction "RS_8") (pintype "passive"))
      (node (ref "USB1") (pin "5") (pinfunction "GND_5") (pintype "passive"))
      (node (ref "V1") (pin "1") (pinfunction "GND_1") (pintype "passive"))
      (node (ref "VD3") (pin "1") (pinfunction "A_1") (pintype "passive"))
      (node (ref "Y1") (pin "3") (pinfunction "g_3") (pintype "passive"))
    )
    (net (code "85") (name "Net-(CON1-Pad1)") (class "Default")
      (node (ref "CON1") (pin "1") (pintype "power_in"))
      (node (ref "F1") (pin "1") (pinfunction "1_1") (pintype "passive"))
      (node (ref "JP2") (pin "1") (pinfunction "1_1") (pintype "passive"))
    )
    (net (code "86") (name "Net-(F1-Pad2)") (class "Default")
      (node (ref "F1") (pin "2") (pinfunction "2_2") (pintype "passive"))
      (node (ref "S1") (pin "3") (pinfunction "3_3") (pintype "passive"))
    )
    (net (code "87") (name "Net-(F2-Pad1)") (class "Default")
      (node (ref "F2") (pin "1") (pinfunction "1_1") (pintype "passive"))
      (node (ref "S1") (pin "4") (pinfunction "4_4") (pintype "passive"))
    )
    (net (code "88") (name "Net-(IC3-C1+)") (class "Default")
      (node (ref "C36") (pin "1") (pinfunction "1_1") (pintype "passive"))
      (node (ref "IC3") (pin "1") (pinfunction "C1+_1") (pintype "passive"))
    )
    (net (code "89") (name "Net-(IC3-C1-)") (class "Default")
      (node (ref "C36") (pin "2") (pinfunction "2_2") (pintype "passive"))
      (node (ref "IC3") (pin "3") (pinfunction "C1-_3") (pintype "passive"))
    )
    (net (code "90") (name "Net-(IC3-C2+)") (class "Default")
      (node (ref "C45") (pin "1") (pinfunction "1_1") (pintype "passive"))
      (node (ref "IC3") (pin "4") (pinfunction "C2+_4") (pintype "passive"))
    )
    (net (code "91") (name "Net-(IC3-C2-)") (class "Default")
      (node (ref "C45") (pin "2") (pinfunction "2_2") (pintype "passive"))
      (node (ref "IC3") (pin "5") (pinfunction "C2-_5") (pintype "passive"))
    )
    (net (code "92") (name "Net-(IC3-R1IN)") (class "Default")
      (node (ref "IC3") (pin "13") (pinfunction "R1IN_13") (pintype "passive"))
      (node (ref "J4") (pin "3") (pinfunction "3_3") (pintype "passive"))
    )
    (net (code "93") (name "Net-(IC3-T1OUT)") (class "Default")
      (node (ref "IC3") (pin "14") (pinfunction "T1OUT_14") (pintype "passive"))
      (node (ref "J4") (pin "2") (pinfunction "2_2") (pintype "passive"))
    )
    (net (code "94") (name "Net-(IC3-VDD)") (class "Default")
      (node (ref "C42") (pin "2") (pinfunction "2_2") (pintype "passive"))
      (node (ref "IC3") (pin "2") (pinfunction "VDD_2") (pintype "passive"))
    )
    (net (code "95") (name "Net-(IC3-VEE)") (class "Default")
      (node (ref "C52") (pin "2") (pinfunction "2_2") (pintype "passive"))
      (node (ref "IC3") (pin "6") (pinfunction "VEE_6") (pintype "passive"))
    )
    (net (code "96") (name "Net-(J3-LED(G)_A)") (class "Default")
      (node (ref "J3") (pin "9") (pinfunction "LED(G)_A_9") (pintype "passive"))
      (node (ref "R35") (pin "1") (pinfunction "1_1") (pintype "passive"))
    )
    (net (code "97") (name "Net-(J3-LED(Y)_A)") (class "Default")
      (node (ref "J3") (pin "12") (pinfunction "LED(Y)_A_12") (pintype "passive"))
      (node (ref "R30") (pin "1") (pinfunction "1_1") (pintype "passive"))
    )
    (net (code "98") (name "Net-(J3-RD+)") (class "Default")
      (node (ref "J3") (pin "3") (pinfunction "RD+_3") (pintype "passive"))
      (node (ref "R26") (pin "2") (pinfunction "2_2") (pintype "passive"))
      (node (ref "U5") (pin "14") (pinfunction "RD+_14") (pintype "passive"))
    )
    (net (code "99") (name "Net-(J3-RD-)") (class "Default")
      (node (ref "J3") (pin "6") (pinfunction "RD-_6") (pintype "passive"))
      (node (ref "R27") (pin "2") (pinfunction "2_2") (pintype "passive"))
      (node (ref "U5") (pin "13") (pinfunction "RD-_13") (pintype "passive"))
    )
    (net (code "100") (name "Net-(J3-TD+)") (class "Default")
      (node (ref "J3") (pin "1") (pinfunction "TD+_1") (pintype "passive"))
      (node (ref "R24") (pin "2") (pinfunction "2_2") (pintype "passive"))
      (node (ref "U5") (pin "17") (pinfunction "TD+_17") (pintype "passive"))
    )
    (net (code "101") (name "Net-(J3-TD-)") (class "Default")
      (node (ref "J3") (pin "2") (pinfunction "TD-_2") (pintype "passive"))
      (node (ref "R25") (pin "2") (pinfunction "2_2") (pintype "passive"))
      (node (ref "U5") (pin "16") (pinfunction "TD-_16") (pintype "passive"))
    )
    (net (code "102") (name "Net-(LED1-A)") (class "Default")
      (node (ref "LED1") (pin "1") (pinfunction "A_1") (pintype "passive"))
      (node (ref "R16") (pin "1") (pinfunction "1_1") (pintype "passive"))
    )
    (net (code "103") (name "Net-(R39-Pad2)") (class "Default")
      (node (ref "R39") (pin "2") (pinfunction "2_2") (pintype "passive"))
      (node (ref "R42") (pin "2") (pinfunction "2_2") (pintype "passive"))
    )
    (net (code "104") (name "Net-(R40-Pad1)") (class "Default")
      (node (ref "R40") (pin "1") (pinfunction "1_1") (pintype "passive"))
      (node (ref "U5") (pin "21") (pinfunction "RESERVED_21") (pintype "passive"))
    )
    (net (code "105") (name "Net-(R41-Pad1)") (class "Default")
      (node (ref "R41") (pin "1") (pinfunction "1_1") (pintype "passive"))
      (node (ref "U5") (pin "20") (pinfunction "RESERVED_20") (pintype "passive"))
    )
    (net (code "106") (name "Net-(U2-BST)") (class "Default")
      (node (ref "C18") (pin "2") (pinfunction "2_2") (pintype "passive"))
      (node (ref "U2") (pin "1") (pinfunction "BST_1") (pintype "passive"))
    )
    (net (code "107") (name "Net-(U2-EN)") (class "Default")
      (node (ref "R14") (pin "1") (pinfunction "1_1") (pintype "passive"))
      (node (ref "U2") (pin "4") (pinfunction "EN_4") (pintype "passive"))
    )
    (net (code "108") (name "Net-(U2-FB)") (class "Default")
      (node (ref "R13") (pin "1") (pinfunction "1_1") (pintype "passive"))
      (node (ref "R15") (pin "2") (pinfunction "2_2") (pintype "passive"))
      (node (ref "U2") (pin "3") (pinfunction "FB_3") (pintype "passive"))
    )
    (net (code "109") (name "Net-(U2-IN)") (class "Default")
      (node (ref "C20") (pin "2") (pinfunction "2_2") (pintype "passive"))
      (node (ref "C21") (pin "2") (pinfunction "2_2") (pintype "passive"))
      (node (ref "R14") (pin "2") (pinfunction "2_2") (pintype "passive"))
      (node (ref "U2") (pin "5") (pinfunction "IN_5") (pintype "passive"))
      (node (ref "VD4") (pin "2") (pinfunction "K_2") (pintype "passive"))
    )
    (net (code "110") (name "Net-(U2-SW)") (class "Default")
      (node (ref "C18") (pin "1") (pinfunction "1_1") (pintype "passive"))
      (node (ref "L1") (pin "1") (pinfunction "1_1") (pintype "passive"))
      (node (ref "U2") (pin "6") (pinfunction "SW_6") (pintype "passive"))
      (node (ref "VD3") (pin "2") (pinfunction "K_2") (pintype "passive"))
    )
    (net (code "111") (name "Net-(U5-LED_SPEED{slash}AN1)") (class "Default")
      (node (ref "R45") (pin "1") (pinfunction "1_1") (pintype "passive"))
      (node (ref "U5") (pin "27") (pinfunction "LED_SPEED/AN1_27") (pintype "passive"))
    )
    (net (code "112") (name "Net-(U5-PFBIN1)") (class "Default")
      (node (ref "C48") (pin "1") (pinfunction "1_1") (pintype "passive"))
      (node (ref "C49") (pin "1") (pinfunction "1_1") (pintype "passive"))
      (node (ref "C50") (pin "1") (pinfunction "1_1") (pintype "passive"))
      (node (ref "C51") (pin "1") (pinfunction "1_1") (pintype "passive"))
      (node (ref "U5") (pin "18") (pinfunction "PFBIN1_18") (pintype "passive"))
      (node (ref "U5") (pin "23") (pinfunction "PFBOUT_23") (pintype "passive"))
      (node (ref "U5") (pin "37") (pinfunction "PFBIN2_37") (pintype "passive"))
    )
    (net (code "113") (name "Net-(U5-PWR_DOWN{slash}INT)") (class "Default")
      (node (ref "R47") (pin "1") (pinfunction "1_1") (pintype "passive"))
      (node (ref "U5") (pin "7") (pinfunction "PWR_DOWN/INT_7") (pintype "passive"))
    )
    (net (code "114") (name "Net-(U5-RBIAS)") (class "Default")
      (node (ref "R48") (pin "1") (pinfunction "1_1") (pintype "passive"))
      (node (ref "U5") (pin "24") (pinfunction "RBIAS_24") (pintype "passive"))
    )
    (net (code "115") (name "Net-(U5-RXD_0{slash}PHYAD1)") (class "Default")
      (node (ref "R36") (pin "1") (pinfunction "1_1") (pintype "passive"))
      (node (ref "U5") (pin "43") (pinfunction "RXD_0/PHYAD1_43") (pintype "passive"))
    )
    (net (code "116") (name "Net-(U5-RXD_1{slash}PHYAD2)") (class "Default")
      (node (ref "R38") (pin "1") (pinfunction "1_1") (pintype "passive"))
      (node (ref "U5") (pin "44") (pinfunction "RXD_1/PHYAD2_44") (pintype "passive"))
    )
    (net (code "117") (name "Net-(U5-TXD_0)") (class "Default")
      (node (ref "R29") (pin "1") (pinfunction "1_1") (pintype "passive"))
      (node (ref "U5") (pin "3") (pinfunction "TXD_0_3") (pintype "passive"))
    )
    (net (code "118") (name "Net-(U5-TXD_1)") (class "Default")
      (node (ref "R31") (pin "1") (pinfunction "1_1") (pintype "passive"))
      (node (ref "U5") (pin "4") (pinfunction "TXD_1_4") (pintype "passive"))
    )
    (net (code "119") (name "Net-(U5-TXD_2)") (class "Default")
      (node (ref "R32") (pin "1") (pinfunction "1_1") (pintype "passive"))
      (node (ref "U5") (pin "5") (pinfunction "TXD_2_5") (pintype "passive"))
    )
    (net (code "120") (name "Net-(U5-TXD_3{slash}SNI_MODE)") (class "Default")
      (node (ref "R34") (pin "1") (pinfunction "1_1") (pintype "passive"))
      (node (ref "U5") (pin "6") (pinfunction "TXD_3/SNI_MODE_6") (pintype "passive"))
    )
    (net (code "121") (name "Net-(U5-TX_EN)") (class "Default")
      (node (ref "R28") (pin "1") (pinfunction "1_1") (pintype "passive"))
      (node (ref "U5") (pin "2") (pinfunction "TX_EN_2") (pintype "passive"))
    )
    (net (code "122") (name "Net-(U6-GND)") (class "Default")
      (node (ref "C35") (pin "1") (pinfunction "1_1") (pintype "passive"))
      (node (ref "U6") (pin "2") (pinfunction "GND_2") (pintype "passive"))
    )
    (net (code "123") (name "Net-(USB1-+5V)") (class "Default")
      (node (ref "F2") (pin "2") (pinfunction "2_2") (pintype "passive"))
      (node (ref "USB1") (pin "1") (pinfunction "+5V_1") (pintype "passive"))
    )
    (net (code "124") (name "Net-(VD4-A)") (class "Default")
      (node (ref "S1") (pin "2") (pinfunction "2_2") (pintype "passive"))
      (node (ref "VD4") (pin "1") (pinfunction "A_1") (pintype "passive"))
    )
    (net (code "125") (name "Net-(Y1-out)") (class "Default")
      (node (ref "C43") (pin "1") (pinfunction "1_1") (pintype "passive"))
      (node (ref "C44") (pin "1") (pinfunction "1_1") (pintype "passive"))
      (node (ref "L3") (pin "1") (pinfunction "1_1") (pintype "passive"))
      (node (ref "Y1") (pin "4") (pinfunction "out_4") (pintype "passive"))
    )
    (net (code "126") (name "unconnected-(IC3-R2IN-Pad8)") (class "Default")
      (node (ref "IC3") (pin "8") (pinfunction "R2IN_8") (pintype "passive+no_connect"))
    )
    (net (code "127") (name "unconnected-(IC3-R2OUT-Pad9)") (class "Default")
      (node (ref "IC3") (pin "9") (pinfunction "R2OUT_9") (pintype "passive+no_connect"))
    )
    (net (code "128") (name "unconnected-(IC3-T2IN-Pad10)") (class "Default")
      (node (ref "IC3") (pin "10") (pinfunction "T2IN_10") (pintype "passive+no_connect"))
    )
    (net (code "129") (name "unconnected-(IC3-T2OUT-Pad7)") (class "Default")
      (node (ref "IC3") (pin "7") (pinfunction "T2OUT_7") (pintype "passive+no_connect"))
    )
    (net (code "130") (name "unconnected-(J2-NC-Pad28)") (class "Default")
      (node (ref "J2") (pin "28") (pinfunction "NC_28") (pintype "passive+no_connect"))
    )
    (net (code "131") (name "unconnected-(J3-NC-Pad7)") (class "Default")
      (node (ref "J3") (pin "7") (pinfunction "NC_7") (pintype "passive+no_connect"))
    )
    (net (code "132") (name "unconnected-(J4-Pad1)") (class "Default")
      (node (ref "J4") (pin "1") (pinfunction "1_1") (pintype "passive+no_connect"))
    )
    (net (code "133") (name "unconnected-(J4-Pad4)") (class "Default")
      (node (ref "J4") (pin "4") (pinfunction "4_4") (pintype "passive+no_connect"))
    )
    (net (code "134") (name "unconnected-(J4-Pad6)") (class "Default")
      (node (ref "J4") (pin "6") (pinfunction "6_6") (pintype "passive+no_connect"))
    )
    (net (code "135") (name "unconnected-(J4-Pad7)") (class "Default")
      (node (ref "J4") (pin "7") (pinfunction "7_7") (pintype "passive+no_connect"))
    )
    (net (code "136") (name "unconnected-(J4-Pad8)") (class "Default")
      (node (ref "J4") (pin "8") (pinfunction "8_8") (pintype "passive+no_connect"))
    )
    (net (code "137") (name "unconnected-(J4-Pad9)") (class "Default")
      (node (ref "J4") (pin "9") (pinfunction "9_9") (pintype "passive+no_connect"))
    )
    (net (code "138") (name "unconnected-(S1-Pad1)") (class "Default")
      (node (ref "S1") (pin "1") (pinfunction "1_1") (pintype "passive"))
    )
    (net (code "139") (name "unconnected-(S1-Pad6)") (class "Default")
      (node (ref "S1") (pin "6") (pinfunction "6_6") (pintype "passive"))
    )
    (net (code "140") (name "unconnected-(U5-25MHz_OUT-Pad25)") (class "Default")
      (node (ref "U5") (pin "25") (pinfunction "25MHz_OUT_25") (pintype "passive+no_connect"))
    )
    (net (code "141") (name "unconnected-(U5-COL{slash}PHYAD0-Pad42)") (class "Default")
      (node (ref "U5") (pin "42") (pinfunction "COL/PHYAD0_42") (pintype "passive+no_connect"))
    )
    (net (code "142") (name "unconnected-(U5-CRS{slash}CRS_DV{slash}LED_CFG-Pad40)") (class "Default")
      (node (ref "U5") (pin "40") (pinfunction "CRS/CRS_DV/LED_CFG_40") (pintype "passive+no_connect"))
    )
    (net (code "143") (name "unconnected-(U5-RXD_2{slash}PHYAD3-Pad45)") (class "Default")
      (node (ref "U5") (pin "45") (pinfunction "RXD_2/PHYAD3_45") (pintype "passive+no_connect"))
    )
    (net (code "144") (name "unconnected-(U5-RXD_3{slash}PHYAD4-Pad46)") (class "Default")
      (node (ref "U5") (pin "46") (pinfunction "RXD_3/PHYAD4_46") (pintype "passive+no_connect"))
    )
    (net (code "145") (name "unconnected-(U5-RX_CLK-Pad38)") (class "Default")
      (node (ref "U5") (pin "38") (pinfunction "RX_CLK_38") (pintype "passive+no_connect"))
    )
    (net (code "146") (name "unconnected-(U5-RX_ER{slash}MDIX_EN-Pad41)") (class "Default")
      (node (ref "U5") (pin "41") (pinfunction "RX_ER/MDIX_EN_41") (pintype "passive+no_connect"))
    )
    (net (code "147") (name "unconnected-(U5-TCK-Pad8)") (class "Default")
      (node (ref "U5") (pin "8") (pinfunction "TCK_8") (pintype "passive"))
    )
    (net (code "148") (name "unconnected-(U5-TDI-Pad12)") (class "Default")
      (node (ref "U5") (pin "12") (pinfunction "TDI_12") (pintype "passive"))
    )
    (net (code "149") (name "unconnected-(U5-TDO-Pad9)") (class "Default")
      (node (ref "U5") (pin "9") (pinfunction "TDO_9") (pintype "passive"))
    )
    (net (code "150") (name "unconnected-(U5-TMS-Pad10)") (class "Default")
      (node (ref "U5") (pin "10") (pinfunction "TMS_10") (pintype "passive"))
    )
    (net (code "151") (name "unconnected-(U5-TRST#-Pad11)") (class "Default")
      (node (ref "U5") (pin "11") (pinfunction "TRST#_11") (pintype "passive"))
    )
    (net (code "152") (name "unconnected-(U5-TX_CLK-Pad1)") (class "Default")
      (node (ref "U5") (pin "1") (pinfunction "TX_CLK_1") (pintype "passive+no_connect"))
    )
    (net (code "153") (name "unconnected-(U5-X2-Pad33)") (class "Default")
      (node (ref "U5") (pin "33") (pinfunction "X2_33") (pintype "passive+no_connect"))
    )
    (net (code "154") (name "unconnected-(U6-Vref-Pad5)") (class "Default")
      (node (ref "U6") (pin "5") (pinfunction "Vref_5") (pintype "passive"))
    )
    (net (code "155") (name "unconnected-(USB1-ID-Pad4)") (class "Default")
      (node (ref "USB1") (pin "4") (pinfunction "ID_4") (pintype "passive"))
    )
    (net (code "156") (name "unconnected-(Y1-g-Pad2)") (class "Default")
      (node (ref "Y1") (pin "2") (pinfunction "g_2") (pintype "passive"))
    )
  )
)
